# Adafruit_ESP8266_Feather.net
KiCad netlist of a schematic drawn in EAGLE
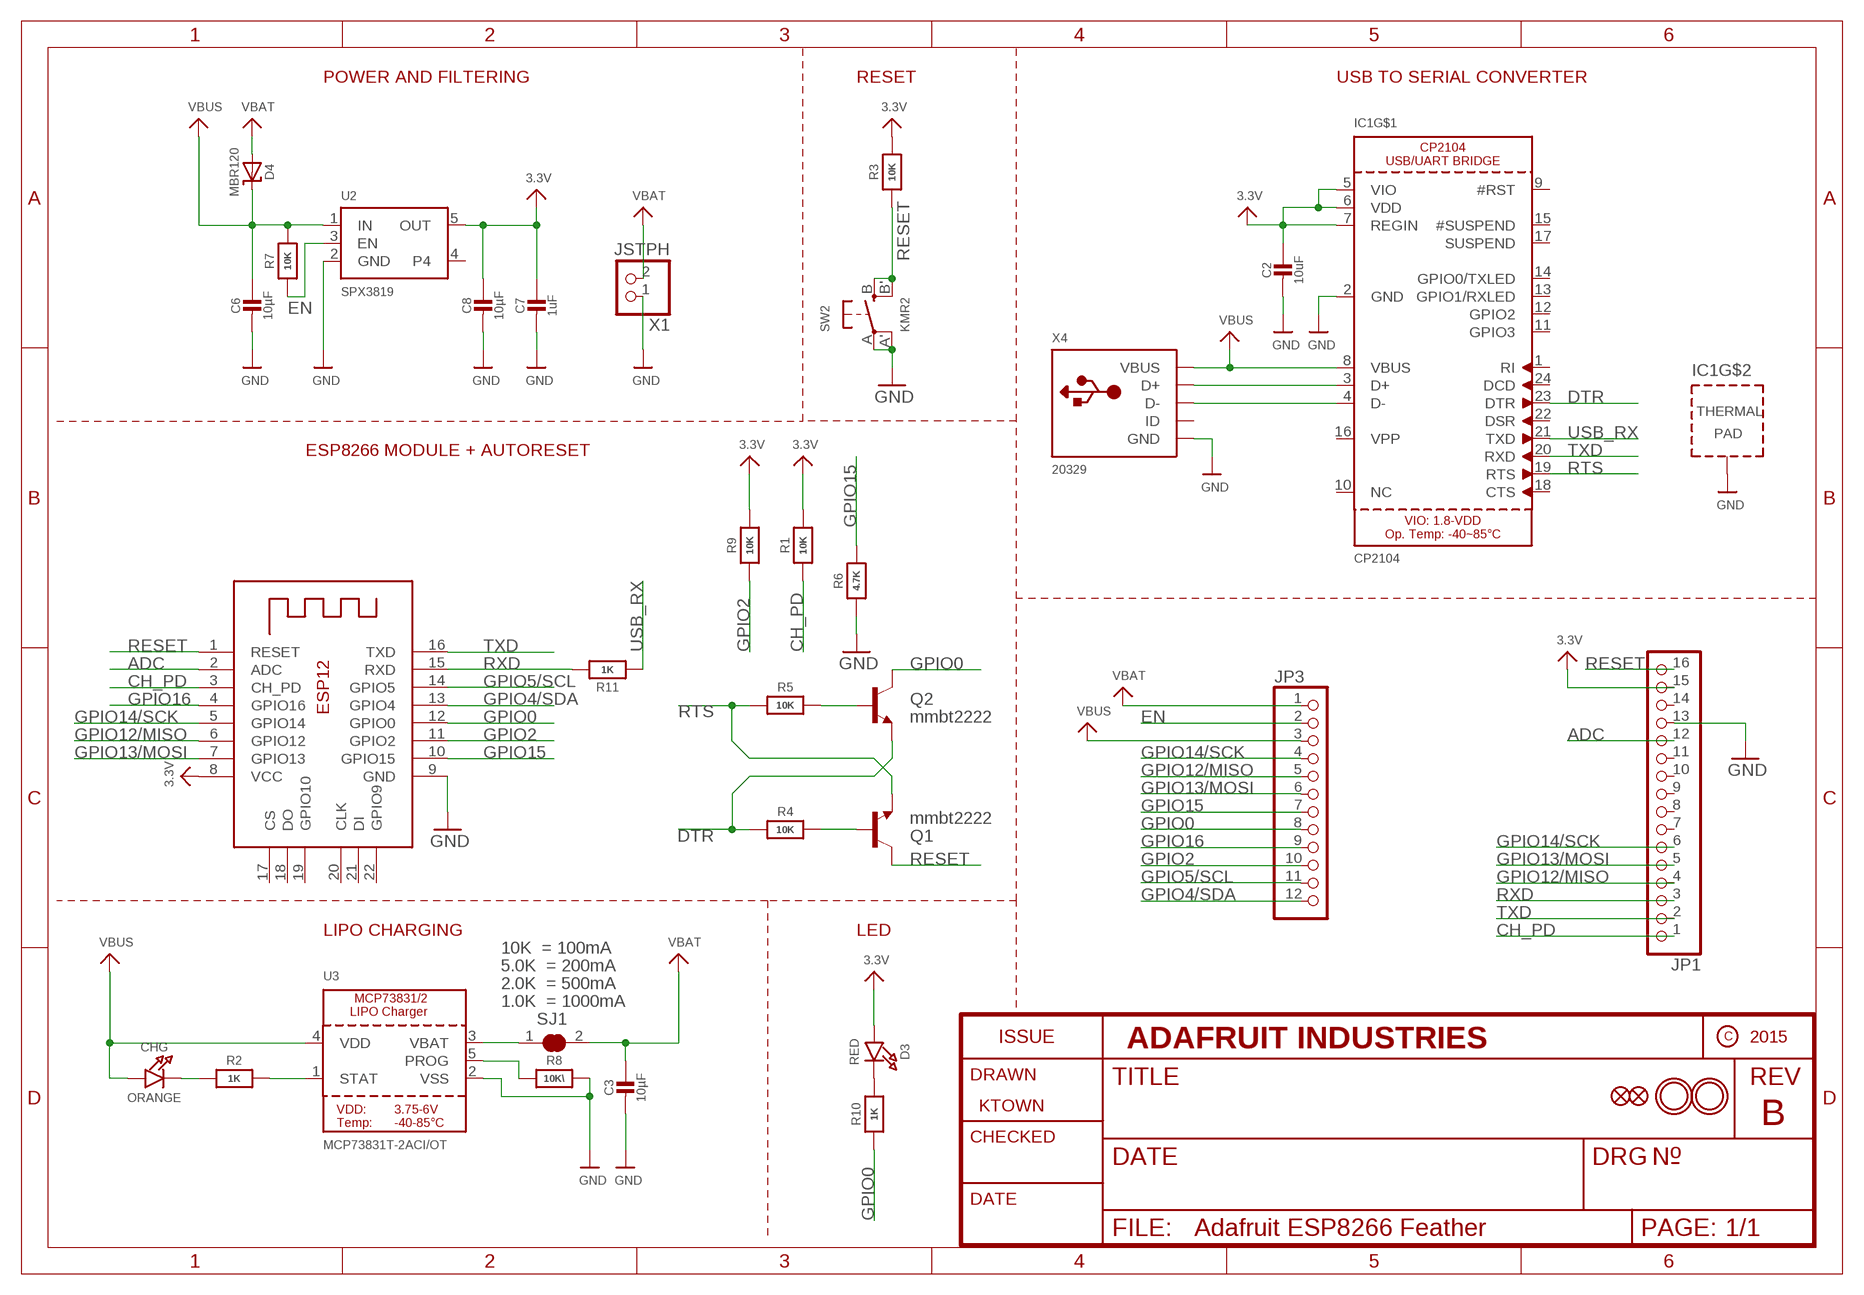
[diagram p0: schematic, sheet 1]

(export (version "E")
  (design (tool "Eeschema 10.0.6"))
  (components
    (comp (ref "C2")
      (value "10uF")
      (footprint "eagle-import:0805-NO")
      (libsource (lib "eagle-import") (part "CAP_CERAMIC0805-NOOUTLINE"))
    )
    (comp (ref "C3")
      (value "10µF")
      (footprint "eagle-import:0805-NO")
      (libsource (lib "eagle-import") (part "CAP_CERAMIC0805-NOOUTLINE"))
    )
    (comp (ref "C6")
      (value "10µF")
      (footprint "eagle-import:0805-NO")
      (libsource (lib "eagle-import") (part "CAP_CERAMIC0805-NOOUTLINE"))
    )
    (comp (ref "C7")
      (value "1uF")
      (footprint "eagle-import:0603-NO")
      (libsource (lib "eagle-import") (part "CAP_CERAMIC0603_NO"))
    )
    (comp (ref "C8")
      (value "10µF")
      (footprint "eagle-import:0805-NO")
      (libsource (lib "eagle-import") (part "CAP_CERAMIC0805-NOOUTLINE"))
    )
    (comp (ref "CHG")
      (value "ORANGE")
      (footprint "eagle-import:CHIPLED_0805_NOOUTLINE")
      (libsource (lib "eagle-import") (part "LED0805_NOOUTLINE"))
    )
    (comp (ref "D3")
      (value "RED")
      (footprint "eagle-import:CHIPLED_0805_NOOUTLINE")
      (libsource (lib "eagle-import") (part "LED0805_NOOUTLINE"))
    )
    (comp (ref "D4")
      (value "MBR120")
      (footprint "eagle-import:SOD-123")
      (libsource (lib "eagle-import") (part "DIODE-SCHOTTKYSOD-123"))
    )
    (comp (ref "IC1")
      (value "CP2104")
      (footprint "eagle-import:QFN24_4MM_SMSC")
      (libsource (lib "eagle-import") (part "CP2104"))
    )
    (comp (ref "JP1")
      (value "HEADER-1X16ROUND")
      (footprint "eagle-import:1X16_ROUND")
      (libsource (lib "eagle-import") (part "HEADER-1X16ROUND"))
    )
    (comp (ref "JP3")
      (value "HEADER-1X12")
      (footprint "eagle-import:1X12_ROUND")
      (libsource (lib "eagle-import") (part "HEADER-1X12"))
    )
    (comp (ref "Q1")
      (value "mmbt2222")
      (footprint "eagle-import:SOT23-3")
      (libsource (lib "eagle-import") (part "TRANSISTOR_NPNSOT23-3"))
    )
    (comp (ref "Q2")
      (value "mmbt2222")
      (footprint "eagle-import:SOT23-3")
      (libsource (lib "eagle-import") (part "TRANSISTOR_NPNSOT23-3"))
    )
    (comp (ref "R1")
      (value "10K")
      (footprint "eagle-import:0603-NO")
      (libsource (lib "eagle-import") (part "RESISTOR_0603_NOOUT"))
    )
    (comp (ref "R2")
      (value "1K")
      (footprint "eagle-import:0603-NO")
      (libsource (lib "eagle-import") (part "RESISTOR_0603_NOOUT"))
    )
    (comp (ref "R3")
      (value "10K")
      (footprint "eagle-import:0603-NO")
      (libsource (lib "eagle-import") (part "RESISTOR_0603_NOOUT"))
    )
    (comp (ref "R4")
      (value "10K")
      (footprint "eagle-import:0603-NO")
      (libsource (lib "eagle-import") (part "RESISTOR_0603_NOOUT"))
    )
    (comp (ref "R5")
      (value "10K")
      (footprint "eagle-import:_0603MP")
      (libsource (lib "eagle-import") (part "RESISTOR_0603MP"))
    )
    (comp (ref "R6")
      (value "4.7K")
      (footprint "eagle-import:0603-NO")
      (libsource (lib "eagle-import") (part "RESISTOR_0603_NOOUT"))
    )
    (comp (ref "R7")
      (value "10K")
      (footprint "eagle-import:0603-NO")
      (libsource (lib "eagle-import") (part "RESISTOR_0603_NOOUT"))
    )
    (comp (ref "R8")
      (value "10K\\")
      (footprint "eagle-import:0603-NO")
      (libsource (lib "eagle-import") (part "RESISTOR_0603_NOOUT"))
    )
    (comp (ref "R9")
      (value "10K")
      (footprint "eagle-import:0603-NO")
      (libsource (lib "eagle-import") (part "RESISTOR_0603_NOOUT"))
    )
    (comp (ref "R10")
      (value "1K")
      (footprint "eagle-import:0603-NO")
      (libsource (lib "eagle-import") (part "RESISTOR_0603_NOOUT"))
    )
    (comp (ref "R11")
      (value "1K")
      (footprint "eagle-import:_0603MP")
      (libsource (lib "eagle-import") (part "RESISTOR_0603MP"))
    )
    (comp (ref "SJ1")
      (value "SOLDERJUMPER_CLOSED")
      (footprint "eagle-import:SOLDERJUMPER_CLOSEDWIRE")
      (libsource (lib "eagle-import") (part "SOLDERJUMPER_CLOSED"))
    )
    (comp (ref "SW2")
      (value "KMR2")
      (footprint "eagle-import:BTN_KMR2_4.6X2.8")
      (libsource (lib "eagle-import") (part "SWITCH_TACT_SMT4.6X2.8"))
    )
    (comp (ref "U$31")
      (value "MOUNTINGHOLE2.5")
      (footprint "eagle-import:MOUNTINGHOLE_2.5_PLATED")
      (libsource (lib "eagle-import") (part "MOUNTINGHOLE2.5"))
    )
    (comp (ref "U$32")
      (value "MOUNTINGHOLE2.5")
      (footprint "eagle-import:MOUNTINGHOLE_2.5_PLATED")
      (libsource (lib "eagle-import") (part "MOUNTINGHOLE2.5"))
    )
    (comp (ref "U$34")
      (value "FIDUCIAL\"\"")
      (footprint "eagle-import:FIDUCIAL_1MM")
      (libsource (lib "eagle-import") (part "FIDUCIAL{dblquote}{dblquote}"))
    )
    (comp (ref "U$35")
      (value "FIDUCIAL\"\"")
      (footprint "eagle-import:FIDUCIAL_1MM")
      (libsource (lib "eagle-import") (part "FIDUCIAL{dblquote}{dblquote}"))
    )
    (comp (ref "U2")
      (value "SPX3819")
      (footprint "eagle-import:SOT23-5")
      (libsource (lib "eagle-import") (part "VREG_SOT23-5"))
    )
    (comp (ref "U3")
      (value "MCP73831T-2ACI/OT")
      (footprint "eagle-import:SOT23-5")
      (libsource (lib "eagle-import") (part "MCP73831/2"))
    )
    (comp (ref "X1")
      (value "JSTPH")
      (footprint "eagle-import:JSTPH2")
      (libsource (lib "eagle-import") (part "CON_JST_PH_2PIN"))
    )
    (comp (ref "X2")
      (value "ESP-12")
      (footprint "eagle-import:ESP-12E")
      (libsource (lib "eagle-import") (part "ESP-12E"))
    )
    (comp (ref "X4")
      (value "20329")
      (footprint "eagle-import:MICRO-USB5+6P-SMD-0.65-B")
      (libsource (lib "eagle-import") (part "MICRO-USB-SMD-B-(10118193-0001LF)-ADASYM"))
    )
  )
  (nets
    (net (code "1") (name "/ADC") (class "Default")
      (node (ref "JP1") (pin "12") (pinfunction "12_12") (pintype "passive"))
      (node (ref "X2") (pin "2") (pinfunction "ADC_2") (pintype "passive"))
    )
    (net (code "2") (name "/CH_PD") (class "Default")
      (node (ref "JP1") (pin "1") (pinfunction "1_1") (pintype "passive"))
      (node (ref "R1") (pin "1") (pinfunction "1_1") (pintype "passive"))
      (node (ref "X2") (pin "3") (pinfunction "CH_PD_3") (pintype "input"))
    )
    (net (code "3") (name "/DTR") (class "Default")
      (node (ref "IC1") (pin "23") (pinfunction "DTR_23") (pintype "output"))
      (node (ref "Q2") (pin "2") (pinfunction "E_2") (pintype "passive"))
      (node (ref "R4") (pin "1") (pinfunction "1_1") (pintype "passive"))
    )
    (net (code "4") (name "/EN") (class "Default")
      (node (ref "JP3") (pin "2") (pinfunction "2_2") (pintype "passive"))
      (node (ref "R7") (pin "1") (pinfunction "1_1") (pintype "passive"))
      (node (ref "U2") (pin "3") (pinfunction "EN_3") (pintype "input"))
    )
    (net (code "5") (name "/GPIO0") (class "Default")
      (node (ref "JP3") (pin "8") (pinfunction "8_8") (pintype "passive"))
      (node (ref "Q2") (pin "3") (pinfunction "C_3") (pintype "passive"))
      (node (ref "R10") (pin "1") (pinfunction "1_1") (pintype "passive"))
      (node (ref "X2") (pin "12") (pinfunction "GPIO0_12") (pintype "bidirectional"))
    )
    (net (code "6") (name "/GPIO2") (class "Default")
      (node (ref "JP3") (pin "10") (pinfunction "10_10") (pintype "passive"))
      (node (ref "R9") (pin "1") (pinfunction "1_1") (pintype "passive"))
      (node (ref "X2") (pin "11") (pinfunction "GPIO2_11") (pintype "bidirectional"))
    )
    (net (code "7") (name "/GPIO4{slash}SDA") (class "Default")
      (node (ref "JP3") (pin "12") (pinfunction "12_12") (pintype "passive"))
      (node (ref "X2") (pin "13") (pinfunction "GPIO4_13") (pintype "bidirectional"))
    )
    (net (code "8") (name "/GPIO5{slash}SCL") (class "Default")
      (node (ref "JP3") (pin "11") (pinfunction "11_11") (pintype "passive"))
      (node (ref "X2") (pin "14") (pinfunction "GPIO5_14") (pintype "bidirectional"))
    )
    (net (code "9") (name "/GPIO12{slash}MISO") (class "Default")
      (node (ref "JP1") (pin "4") (pinfunction "4_4") (pintype "passive"))
      (node (ref "JP3") (pin "5") (pinfunction "5_5") (pintype "passive"))
      (node (ref "X2") (pin "6") (pinfunction "GPIO12_6") (pintype "bidirectional"))
    )
    (net (code "10") (name "/GPIO13{slash}MOSI") (class "Default")
      (node (ref "JP1") (pin "5") (pinfunction "5_5") (pintype "passive"))
      (node (ref "JP3") (pin "6") (pinfunction "6_6") (pintype "passive"))
      (node (ref "X2") (pin "7") (pinfunction "GPIO13_7") (pintype "bidirectional"))
    )
    (net (code "11") (name "/GPIO14{slash}SCK") (class "Default")
      (node (ref "JP1") (pin "6") (pinfunction "6_6") (pintype "passive"))
      (node (ref "JP3") (pin "4") (pinfunction "4_4") (pintype "passive"))
      (node (ref "X2") (pin "5") (pinfunction "GPIO14_5") (pintype "bidirectional"))
    )
    (net (code "12") (name "/GPIO15") (class "Default")
      (node (ref "JP3") (pin "7") (pinfunction "7_7") (pintype "passive"))
      (node (ref "R6") (pin "2") (pinfunction "2_2") (pintype "passive"))
      (node (ref "X2") (pin "10") (pinfunction "GPIO15_10") (pintype "bidirectional"))
    )
    (net (code "13") (name "/GPIO16") (class "Default")
      (node (ref "JP3") (pin "9") (pinfunction "9_9") (pintype "passive"))
      (node (ref "X2") (pin "4") (pinfunction "GPIO16_4") (pintype "bidirectional"))
    )
    (net (code "14") (name "/RESET") (class "Default")
      (node (ref "JP1") (pin "16") (pinfunction "16_16") (pintype "passive"))
      (node (ref "Q1") (pin "3") (pinfunction "C_3") (pintype "passive"))
      (node (ref "R3") (pin "1") (pinfunction "1_1") (pintype "passive"))
      (node (ref "SW2") (pin "B") (pinfunction "S_B") (pintype "passive"))
      (node (ref "SW2") (pin "B'") (pinfunction "S1_B'") (pintype "passive"))
      (node (ref "X2") (pin "1") (pinfunction "RESET_1") (pintype "input"))
    )
    (net (code "15") (name "/RTS") (class "Default")
      (node (ref "IC1") (pin "19") (pinfunction "RTS_19") (pintype "output"))
      (node (ref "Q1") (pin "2") (pinfunction "E_2") (pintype "passive"))
      (node (ref "R5") (pin "1") (pinfunction "1_1") (pintype "passive"))
    )
    (net (code "16") (name "/RXD") (class "Default")
      (node (ref "JP1") (pin "3") (pinfunction "3_3") (pintype "passive"))
      (node (ref "R11") (pin "2") (pinfunction "2_2") (pintype "passive"))
      (node (ref "X2") (pin "15") (pinfunction "RXD_15") (pintype "input"))
    )
    (net (code "17") (name "/TXD") (class "Default")
      (node (ref "IC1") (pin "20") (pinfunction "RXD_20") (pintype "input"))
      (node (ref "JP1") (pin "2") (pinfunction "2_2") (pintype "passive"))
      (node (ref "X2") (pin "16") (pinfunction "TXD_16") (pintype "output"))
    )
    (net (code "18") (name "/USB_RX") (class "Default")
      (node (ref "IC1") (pin "21") (pinfunction "TXD_21") (pintype "output"))
      (node (ref "R11") (pin "1") (pinfunction "1_1") (pintype "passive"))
    )
    (net (code "19") (name "3.3V") (class "Default")
      (node (ref "C2") (pin "1") (pinfunction "1_1") (pintype "passive"))
      (node (ref "C7") (pin "1") (pinfunction "1_1") (pintype "passive"))
      (node (ref "C8") (pin "1") (pinfunction "1_1") (pintype "passive"))
      (node (ref "D3") (pin "A") (pinfunction "A_A") (pintype "passive"))
      (node (ref "IC1") (pin "5") (pinfunction "VIO_5") (pintype "power_in"))
      (node (ref "IC1") (pin "6") (pinfunction "VDD_6") (pintype "power_in"))
      (node (ref "IC1") (pin "7") (pinfunction "REGIN_7") (pintype "power_in"))
      (node (ref "JP1") (pin "15") (pinfunction "15_15") (pintype "passive"))
      (node (ref "R1") (pin "2") (pinfunction "2_2") (pintype "passive"))
      (node (ref "R3") (pin "2") (pinfunction "2_2") (pintype "passive"))
      (node (ref "R9") (pin "2") (pinfunction "2_2") (pintype "passive"))
      (node (ref "U2") (pin "5") (pinfunction "OUT_5") (pintype "power_in"))
      (node (ref "X2") (pin "8") (pinfunction "VCC_8") (pintype "power_in"))
    )
    (net (code "20") (name "GND") (class "Default")
      (node (ref "C2") (pin "2") (pinfunction "2_2") (pintype "passive"))
      (node (ref "C3") (pin "2") (pinfunction "2_2") (pintype "passive"))
      (node (ref "C6") (pin "2") (pinfunction "2_2") (pintype "passive"))
      (node (ref "C7") (pin "2") (pinfunction "2_2") (pintype "passive"))
      (node (ref "C8") (pin "2") (pinfunction "2_2") (pintype "passive"))
      (node (ref "IC1") (pin "2") (pinfunction "GND_2") (pintype "power_in"))
      (node (ref "IC1") (pin "THERM") (pinfunction "TP_THERM") (pintype "power_in"))
      (node (ref "JP1") (pin "13") (pinfunction "13_13") (pintype "passive"))
      (node (ref "R6") (pin "1") (pinfunction "1_1") (pintype "passive"))
      (node (ref "R8") (pin "2") (pinfunction "2_2") (pintype "passive"))
      (node (ref "SW2") (pin "A") (pinfunction "P_A") (pintype "passive"))
      (node (ref "SW2") (pin "A'") (pinfunction "P1_A'") (pintype "passive"))
      (node (ref "U2") (pin "2") (pinfunction "GND_2") (pintype "power_in"))
      (node (ref "U3") (pin "2") (pinfunction "VSS_2") (pintype "power_in"))
      (node (ref "X1") (pin "1") (pinfunction "1_1") (pintype "passive"))
      (node (ref "X2") (pin "9") (pinfunction "GND_9") (pintype "power_in"))
      (node (ref "X4") (pin "5") (pinfunction "GND_5") (pintype "power_in"))
      (node (ref "X4") (pin "S1") (pinfunction "GND_S1") (pintype "power_in"))
      (node (ref "X4") (pin "S2") (pinfunction "GND_S2") (pintype "power_in"))
      (node (ref "X4") (pin "S3") (pinfunction "GND_S3") (pintype "power_in"))
      (node (ref "X4") (pin "S4") (pinfunction "GND_S4") (pintype "power_in"))
      (node (ref "X4") (pin "S5") (pinfunction "GND_S5") (pintype "power_in"))
      (node (ref "X4") (pin "S6") (pinfunction "GND_S6") (pintype "power_in"))
    )
    (net (code "21") (name "Net-(CHG-PadC)") (class "Default")
      (node (ref "CHG") (pin "C") (pinfunction "C_C") (pintype "passive"))
      (node (ref "R2") (pin "1") (pinfunction "1_1") (pintype "passive"))
    )
    (net (code "22") (name "Net-(D3-PadC)") (class "Default")
      (node (ref "D3") (pin "C") (pinfunction "C_C") (pintype "passive"))
      (node (ref "R10") (pin "2") (pinfunction "2_2") (pintype "passive"))
    )
    (net (code "23") (name "Net-(IC1A-D+)") (class "Default")
      (node (ref "IC1") (pin "3") (pinfunction "D+_3") (pintype "bidirectional"))
      (node (ref "X4") (pin "3") (pinfunction "D+_3") (pintype "bidirectional"))
    )
    (net (code "24") (name "Net-(IC1A-D-)") (class "Default")
      (node (ref "IC1") (pin "4") (pinfunction "D-_4") (pintype "bidirectional"))
      (node (ref "X4") (pin "2") (pinfunction "D-_2") (pintype "bidirectional"))
    )
    (net (code "25") (name "Net-(Q1-B)") (class "Default")
      (node (ref "Q1") (pin "1") (pinfunction "B_1") (pintype "passive"))
      (node (ref "R4") (pin "2") (pinfunction "2_2") (pintype "passive"))
    )
    (net (code "26") (name "Net-(Q2-B)") (class "Default")
      (node (ref "Q2") (pin "1") (pinfunction "B_1") (pintype "passive"))
      (node (ref "R5") (pin "2") (pinfunction "2_2") (pintype "passive"))
    )
    (net (code "27") (name "Net-(U3-PROG)") (class "Default")
      (node (ref "R8") (pin "1") (pinfunction "1_1") (pintype "passive"))
      (node (ref "U3") (pin "5") (pinfunction "PROG_5") (pintype "input"))
    )
    (net (code "28") (name "Net-(U3-STAT)") (class "Default")
      (node (ref "R2") (pin "2") (pinfunction "2_2") (pintype "passive"))
      (node (ref "U3") (pin "1") (pinfunction "STAT_1") (pintype "output"))
    )
    (net (code "29") (name "Net-(U3-VBAT)") (class "Default")
      (node (ref "SJ1") (pin "1") (pinfunction "1_1") (pintype "passive"))
      (node (ref "U3") (pin "3") (pinfunction "VBAT_3") (pintype "power_in"))
    )
    (net (code "30") (name "VBAT") (class "Default")
      (node (ref "C3") (pin "1") (pinfunction "1_1") (pintype "passive"))
      (node (ref "D4") (pin "A") (pinfunction "A_A") (pintype "passive"))
      (node (ref "JP3") (pin "1") (pinfunction "1_1") (pintype "passive"))
      (node (ref "SJ1") (pin "2") (pinfunction "2_2") (pintype "passive"))
      (node (ref "X1") (pin "2") (pinfunction "2_2") (pintype "passive"))
    )
    (net (code "31") (name "VBUS") (class "Default")
      (node (ref "C6") (pin "1") (pinfunction "1_1") (pintype "passive"))
      (node (ref "CHG") (pin "A") (pinfunction "A_A") (pintype "passive"))
      (node (ref "D4") (pin "C") (pinfunction "C_C") (pintype "passive"))
      (node (ref "IC1") (pin "8") (pinfunction "VBUS_8") (pintype "power_in"))
      (node (ref "JP3") (pin "3") (pinfunction "3_3") (pintype "passive"))
      (node (ref "R7") (pin "2") (pinfunction "2_2") (pintype "passive"))
      (node (ref "U2") (pin "1") (pinfunction "IN_1") (pintype "power_in"))
      (node (ref "U3") (pin "4") (pinfunction "VDD_4") (pintype "power_in"))
      (node (ref "X4") (pin "1") (pinfunction "VBUS_1") (pintype "power_in"))
    )
    (net (code "32") (name "unconnected-(IC1A-#RST-Pad9)") (class "Default")
      (node (ref "IC1") (pin "9") (pinfunction "#RST_9") (pintype "bidirectional"))
    )
    (net (code "33") (name "unconnected-(IC1A-#SUSPEND-Pad15)") (class "Default")
      (node (ref "IC1") (pin "15") (pinfunction "#SUSPEND_15") (pintype "output"))
    )
    (net (code "34") (name "unconnected-(IC1A-CTS-Pad18)") (class "Default")
      (node (ref "IC1") (pin "18") (pinfunction "CTS_18") (pintype "input"))
    )
    (net (code "35") (name "unconnected-(IC1A-DCD-Pad24)") (class "Default")
      (node (ref "IC1") (pin "24") (pinfunction "DCD_24") (pintype "input"))
    )
    (net (code "36") (name "unconnected-(IC1A-DSR-Pad22)") (class "Default")
      (node (ref "IC1") (pin "22") (pinfunction "DSR_22") (pintype "input"))
    )
    (net (code "37") (name "unconnected-(IC1A-GPIO0{slash}TXLED-Pad14)") (class "Default")
      (node (ref "IC1") (pin "14") (pinfunction "GPIO0/TXLED_14") (pintype "bidirectional"))
    )
    (net (code "38") (name "unconnected-(IC1A-GPIO1{slash}RXLED-Pad13)") (class "Default")
      (node (ref "IC1") (pin "13") (pinfunction "GPIO1/RXLED_13") (pintype "bidirectional"))
    )
    (net (code "39") (name "unconnected-(IC1A-GPIO2-Pad12)") (class "Default")
      (node (ref "IC1") (pin "12") (pinfunction "GPIO2_12") (pintype "bidirectional"))
    )
    (net (code "40") (name "unconnected-(IC1A-GPIO3-Pad11)") (class "Default")
      (node (ref "IC1") (pin "11") (pinfunction "GPIO3_11") (pintype "bidirectional"))
    )
    (net (code "41") (name "unconnected-(IC1A-NC-Pad10)") (class "Default")
      (node (ref "IC1") (pin "10") (pinfunction "NC_10") (pintype "no_connect"))
    )
    (net (code "42") (name "unconnected-(IC1A-RI-Pad1)") (class "Default")
      (node (ref "IC1") (pin "1") (pinfunction "RI_1") (pintype "input"))
    )
    (net (code "43") (name "unconnected-(IC1A-SUSPEND-Pad17)") (class "Default")
      (node (ref "IC1") (pin "17") (pinfunction "SUSPEND_17") (pintype "output"))
    )
    (net (code "44") (name "unconnected-(IC1A-VPP-Pad16)") (class "Default")
      (node (ref "IC1") (pin "16") (pinfunction "VPP_16") (pintype "bidirectional"))
    )
    (net (code "45") (name "unconnected-(JP1-Pad7)") (class "Default")
      (node (ref "JP1") (pin "7") (pinfunction "7_7") (pintype "passive"))
    )
    (net (code "46") (name "unconnected-(JP1-Pad8)") (class "Default")
      (node (ref "JP1") (pin "8") (pinfunction "8_8") (pintype "passive"))
    )
    (net (code "47") (name "unconnected-(JP1-Pad9)") (class "Default")
      (node (ref "JP1") (pin "9") (pinfunction "9_9") (pintype "passive"))
    )
    (net (code "48") (name "unconnected-(JP1-Pad10)") (class "Default")
      (node (ref "JP1") (pin "10") (pinfunction "10_10") (pintype "passive"))
    )
    (net (code "49") (name "unconnected-(JP1-Pad11)") (class "Default")
      (node (ref "JP1") (pin "11") (pinfunction "11_11") (pintype "passive"))
    )
    (net (code "50") (name "unconnected-(JP1-Pad14)") (class "Default")
      (node (ref "JP1") (pin "14") (pinfunction "14_14") (pintype "passive"))
    )
    (net (code "51") (name "unconnected-(U2-P4-Pad4)") (class "Default")
      (node (ref "U2") (pin "4") (pinfunction "P4_4") (pintype "bidirectional"))
    )
    (net (code "52") (name "unconnected-(X2-CLK-Pad20)") (class "Default")
      (node (ref "X2") (pin "20") (pinfunction "CLK_20") (pintype "bidirectional"))
    )
    (net (code "53") (name "unconnected-(X2-CS-Pad17)") (class "Default")
      (node (ref "X2") (pin "17") (pinfunction "CS_17") (pintype "bidirectional"))
    )
    (net (code "54") (name "unconnected-(X2-DI-Pad21)") (class "Default")
      (node (ref "X2") (pin "21") (pinfunction "DI_21") (pintype "bidirectional"))
    )
    (net (code "55") (name "unconnected-(X2-DO-Pad18)") (class "Default")
      (node (ref "X2") (pin "18") (pinfunction "DO_18") (pintype "bidirectional"))
    )
    (net (code "56") (name "unconnected-(X2-GPIO9-Pad22)") (class "Default")
      (node (ref "X2") (pin "22") (pinfunction "GPIO9_22") (pintype "bidirectional"))
    )
    (net (code "57") (name "unconnected-(X2-GPIO10-Pad19)") (class "Default")
      (node (ref "X2") (pin "19") (pinfunction "GPIO10_19") (pintype "bidirectional"))
    )
    (net (code "58") (name "unconnected-(X4-ID-Pad4)") (class "Default")
      (node (ref "X4") (pin "4") (pinfunction "ID_4") (pintype "bidirectional"))
    )
  )
)
